# Clock_Extension.net
KiCad netlist of a schematic drawn in EAGLE
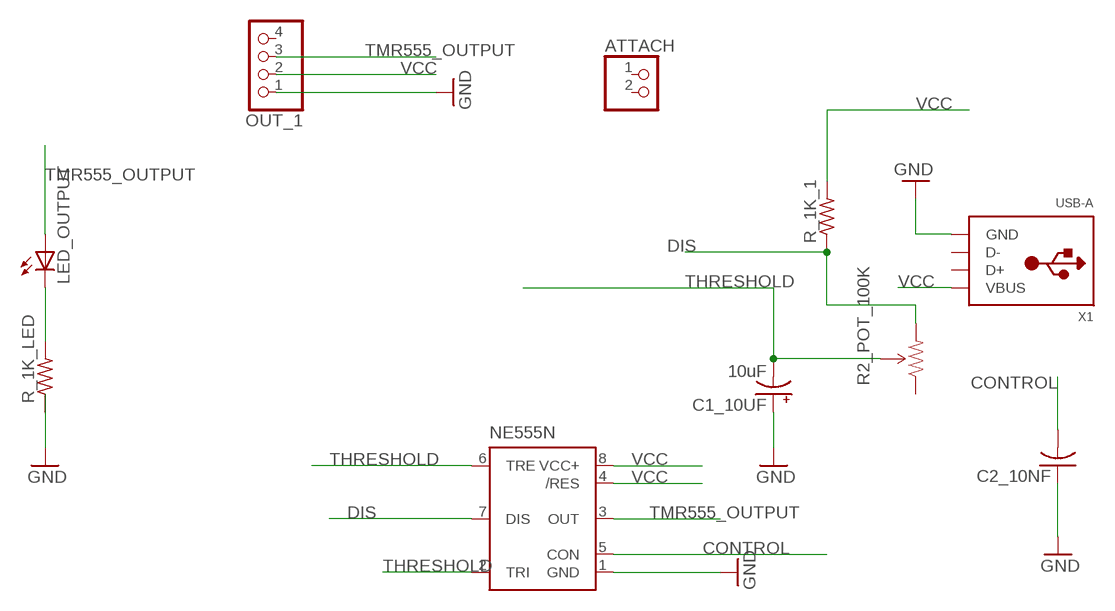
[diagram p0: schematic, sheet 1]

(export (version "E")
  (design (tool "Eeschema 10.0.6"))
  (components
    (comp (ref "ATTACH")
      (value "PINHD-1X2")
      (footprint "eagle-import:1X02")
      (libsource (lib "eagle-import") (part "PINHD-1X2"))
    )
    (comp (ref "C1_10UF")
      (value "10uF")
      (footprint "eagle-import:EIA3216")
      (libsource (lib "eagle-import") (part "10UF-16V-10%(TANT)"))
    )
    (comp (ref "C2_10NF")
      (value "C-USC1206")
      (footprint "eagle-import:C1206")
      (libsource (lib "eagle-import") (part "C-USC1206"))
    )
    (comp (ref "LED_OUTPUT")
      (value "LEDSMT1206")
      (footprint "eagle-import:1206")
      (libsource (lib "eagle-import") (part "LEDSMT1206"))
    )
    (comp (ref "NE555N")
      (value "NE555D")
      (footprint "eagle-import:SO08")
      (libsource (lib "eagle-import") (part "NE555D"))
    )
    (comp (ref "OUT_1")
      (value "PINHD-1X4")
      (footprint "eagle-import:1X04")
      (libsource (lib "eagle-import") (part "PINHD-1X4"))
    )
    (comp (ref "R2_POT_100K")
      (value "TRIMPOTPTH")
      (footprint "eagle-import:TRIM_POT_PTH")
      (libsource (lib "eagle-import") (part "TRIMPOTPTH"))
    )
    (comp (ref "R_1K_1")
      (value "R-US_R1206")
      (footprint "eagle-import:R1206")
      (libsource (lib "eagle-import") (part "R-US_R1206"))
    )
    (comp (ref "R_1K_LED")
      (value "R-US_R1206")
      (footprint "eagle-import:R1206")
      (libsource (lib "eagle-import") (part "R-US_R1206"))
    )
    (comp (ref "X1")
      (value "USB-A")
      (footprint "eagle-import:MOLEX_480371000")
      (libsource (lib "eagle-import") (part "USB-A"))
    )
  )
  (nets
    (net (code "1") (name "/CONTROL") (class "Default")
      (node (ref "C2_10NF") (pin "2") (pinfunction "2_2") (pintype "passive"))
      (node (ref "NE555N") (pin "5") (pinfunction "CON_5") (pintype "input"))
    )
    (net (code "2") (name "/DIS") (class "Default")
      (node (ref "NE555N") (pin "7") (pinfunction "DIS_7") (pintype "input"))
      (node (ref "R2_POT_100K") (pin "3") (pinfunction "CW_3") (pintype "passive"))
      (node (ref "R_1K_1") (pin "1") (pinfunction "1_1") (pintype "passive"))
    )
    (net (code "3") (name "/THRESHOLD") (class "Default")
      (node (ref "C1_10UF") (pin "C") (pinfunction "-_C") (pintype "passive"))
      (node (ref "NE555N") (pin "2") (pinfunction "TRI_2") (pintype "input"))
      (node (ref "NE555N") (pin "6") (pinfunction "TRE_6") (pintype "input"))
      (node (ref "R2_POT_100K") (pin "2") (pinfunction "WIPER_2") (pintype "passive"))
    )
    (net (code "4") (name "/TMR555_OUTPUT") (class "Default")
      (node (ref "LED_OUTPUT") (pin "A") (pinfunction "A_A") (pintype "passive"))
      (node (ref "NE555N") (pin "3") (pinfunction "OUT_3") (pintype "output"))
      (node (ref "OUT_1") (pin "3") (pinfunction "3_3") (pintype "passive"))
    )
    (net (code "5") (name "/VCC") (class "Default")
      (node (ref "NE555N") (pin "4") (pinfunction "/RES_4") (pintype "input"))
      (node (ref "NE555N") (pin "8") (pinfunction "VCC+_8") (pintype "power_in"))
      (node (ref "OUT_1") (pin "2") (pinfunction "2_2") (pintype "passive"))
      (node (ref "R_1K_1") (pin "2") (pinfunction "2_2") (pintype "passive"))
      (node (ref "X1") (pin "1") (pinfunction "VBUS_1") (pintype "power_in"))
    )
    (net (code "6") (name "GND") (class "Default")
      (node (ref "C1_10UF") (pin "A") (pinfunction "+_A") (pintype "passive"))
      (node (ref "C2_10NF") (pin "1") (pinfunction "1_1") (pintype "passive"))
      (node (ref "NE555N") (pin "1") (pinfunction "GND_1") (pintype "power_in"))
      (node (ref "OUT_1") (pin "1") (pinfunction "1_1") (pintype "passive"))
      (node (ref "R_1K_LED") (pin "1") (pinfunction "1_1") (pintype "passive"))
      (node (ref "X1") (pin "4") (pinfunction "GND_4") (pintype "power_in"))
    )
    (net (code "7") (name "Net-(LED_OUTPUT-PadC)") (class "Default")
      (node (ref "LED_OUTPUT") (pin "C") (pinfunction "C_C") (pintype "passive"))
      (node (ref "R_1K_LED") (pin "2") (pinfunction "2_2") (pintype "passive"))
    )
    (net (code "8") (name "unconnected-(ATTACH-Pad1)") (class "Default")
      (node (ref "ATTACH") (pin "1") (pinfunction "1_1") (pintype "passive"))
    )
    (net (code "9") (name "unconnected-(ATTACH-Pad2)") (class "Default")
      (node (ref "ATTACH") (pin "2") (pinfunction "2_2") (pintype "passive"))
    )
    (net (code "10") (name "unconnected-(OUT_1-Pad4)") (class "Default")
      (node (ref "OUT_1") (pin "4") (pinfunction "4_4") (pintype "passive"))
    )
    (net (code "11") (name "unconnected-(R2_POT_100K-CCW-Pad1)") (class "Default")
      (node (ref "R2_POT_100K") (pin "1") (pinfunction "CCW_1") (pintype "passive"))
    )
    (net (code "12") (name "unconnected-(X1-D+-Pad3)") (class "Default")
      (node (ref "X1") (pin "3") (pinfunction "D+_3") (pintype "bidirectional"))
    )
    (net (code "13") (name "unconnected-(X1-D--Pad2)") (class "Default")
      (node (ref "X1") (pin "2") (pinfunction "D-_2") (pintype "bidirectional"))
    )
  )
)
